# attiny45light.net
KiCad netlist of a schematic drawn in EAGLE
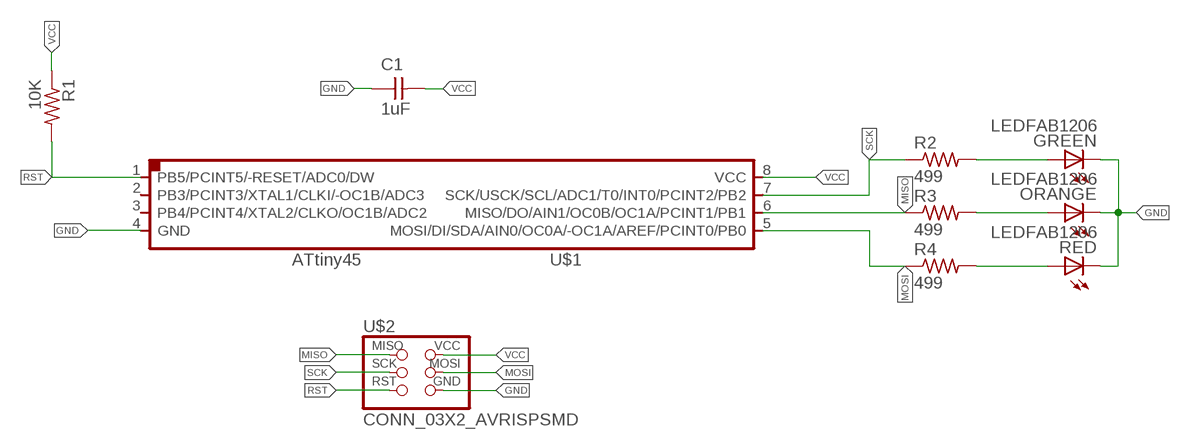
[diagram p0: schematic, sheet 1]

(export (version "E")
  (design (tool "Eeschema 10.0.6"))
  (components
    (comp (ref "C1")
      (value "1uF")
      (footprint "eagle-import:C1206FAB")
      (libsource (lib "eagle-import") (part "CAP_UNPOLARIZEDFAB"))
    )
    (comp (ref "GREEN")
      (value "LEDFAB1206")
      (footprint "eagle-import:LED1206FAB")
      (libsource (lib "eagle-import") (part "LEDFAB1206"))
    )
    (comp (ref "ORANGE")
      (value "LEDFAB1206")
      (footprint "eagle-import:LED1206FAB")
      (libsource (lib "eagle-import") (part "LEDFAB1206"))
    )
    (comp (ref "R1")
      (value "10K")
      (footprint "eagle-import:R1206FAB")
      (libsource (lib "eagle-import") (part "R1206FAB"))
    )
    (comp (ref "R2")
      (value "499")
      (footprint "eagle-import:R1206FAB")
      (libsource (lib "eagle-import") (part "R1206FAB"))
    )
    (comp (ref "R3")
      (value "499")
      (footprint "eagle-import:R1206FAB")
      (libsource (lib "eagle-import") (part "R1206FAB"))
    )
    (comp (ref "R4")
      (value "499")
      (footprint "eagle-import:R1206FAB")
      (libsource (lib "eagle-import") (part "R1206FAB"))
    )
    (comp (ref "RED")
      (value "LEDFAB1206")
      (footprint "eagle-import:LED1206FAB")
      (libsource (lib "eagle-import") (part "LEDFAB1206"))
    )
    (comp (ref "U$1")
      (value "UC_ATTINY45SI")
      (footprint "eagle-import:SOIC8")
      (libsource (lib "eagle-import") (part "UC_ATTINY45SI"))
    )
    (comp (ref "U$2")
      (value "CONN_03X2_AVRISPSMD")
      (footprint "eagle-import:2X03SMD")
      (libsource (lib "eagle-import") (part "CONN_03X2_AVRISPSMD"))
    )
  )
  (nets
    (net (code "1") (name "GND") (class "Default")
      (node (ref "C1") (pin "1") (pinfunction "1_1") (pintype "passive"))
      (node (ref "GREEN") (pin "2") (pinfunction "C_2") (pintype "passive"))
      (node (ref "ORANGE") (pin "2") (pinfunction "C_2") (pintype "passive"))
      (node (ref "RED") (pin "2") (pinfunction "C_2") (pintype "passive"))
      (node (ref "U$1") (pin "4") (pinfunction "GND_4") (pintype "bidirectional"))
      (node (ref "U$2") (pin "6") (pinfunction "GND_6") (pintype "passive"))
    )
    (net (code "2") (name "MISO") (class "Default")
      (node (ref "R3") (pin "1") (pinfunction "1_1") (pintype "passive"))
      (node (ref "U$1") (pin "6") (pinfunction "MISO/DO/AIN1/OC0B/OC1A/PCINT1/PB1_6") (pintype "bidirectional"))
      (node (ref "U$2") (pin "1") (pinfunction "MISO_1") (pintype "passive"))
    )
    (net (code "3") (name "MOSI") (class "Default")
      (node (ref "R4") (pin "1") (pinfunction "1_1") (pintype "passive"))
      (node (ref "U$1") (pin "5") (pinfunction "MOSI/DI/SDA/AIN0/OC0A/-OC1A/AREF/PCINT0/PB0_5") (pintype "bidirectional"))
      (node (ref "U$2") (pin "4") (pinfunction "MOSI_4") (pintype "passive"))
    )
    (net (code "4") (name "Net-(GREEN-A)") (class "Default")
      (node (ref "GREEN") (pin "1") (pinfunction "A_1") (pintype "passive"))
      (node (ref "R2") (pin "2") (pinfunction "2_2") (pintype "passive"))
    )
    (net (code "5") (name "Net-(ORANGE-A)") (class "Default")
      (node (ref "ORANGE") (pin "1") (pinfunction "A_1") (pintype "passive"))
      (node (ref "R3") (pin "2") (pinfunction "2_2") (pintype "passive"))
    )
    (net (code "6") (name "Net-(RED-A)") (class "Default")
      (node (ref "R4") (pin "2") (pinfunction "2_2") (pintype "passive"))
      (node (ref "RED") (pin "1") (pinfunction "A_1") (pintype "passive"))
    )
    (net (code "7") (name "RST") (class "Default")
      (node (ref "R1") (pin "2") (pinfunction "2_2") (pintype "passive"))
      (node (ref "U$1") (pin "1") (pinfunction "PB5/PCINT5/-RESET/ADC0/DW_1") (pintype "bidirectional"))
      (node (ref "U$2") (pin "5") (pinfunction "RST_5") (pintype "passive"))
    )
    (net (code "8") (name "SCK") (class "Default")
      (node (ref "R2") (pin "1") (pinfunction "1_1") (pintype "passive"))
      (node (ref "U$1") (pin "7") (pinfunction "SCK/USCK/SCL/ADC1/T0/INT0/PCINT2/PB2_7") (pintype "bidirectional"))
      (node (ref "U$2") (pin "3") (pinfunction "SCK_3") (pintype "passive"))
    )
    (net (code "9") (name "VCC") (class "Default")
      (node (ref "C1") (pin "2") (pinfunction "2_2") (pintype "passive"))
      (node (ref "R1") (pin "1") (pinfunction "1_1") (pintype "passive"))
      (node (ref "U$1") (pin "8") (pinfunction "VCC_8") (pintype "bidirectional"))
      (node (ref "U$2") (pin "2") (pinfunction "VCC_2") (pintype "passive"))
    )
    (net (code "10") (name "unconnected-(U$1-PB3{slash}PCINT3{slash}XTAL1{slash}CLKI{slash}-OC1B{slash}ADC3-Pad2)") (class "Default")
      (node (ref "U$1") (pin "2") (pinfunction "PB3/PCINT3/XTAL1/CLKI/-OC1B/ADC3_2") (pintype "bidirectional"))
    )
    (net (code "11") (name "unconnected-(U$1-PB4{slash}PCINT4{slash}XTAL2{slash}CLKO{slash}OC1B{slash}ADC2-Pad3)") (class "Default")
      (node (ref "U$1") (pin "3") (pinfunction "PB4/PCINT4/XTAL2/CLKO/OC1B/ADC2_3") (pintype "bidirectional"))
    )
  )
)
